# SCH_circuit_board_2023-10-30.net
KiCad netlist of a schematic drawn in EasyEDA
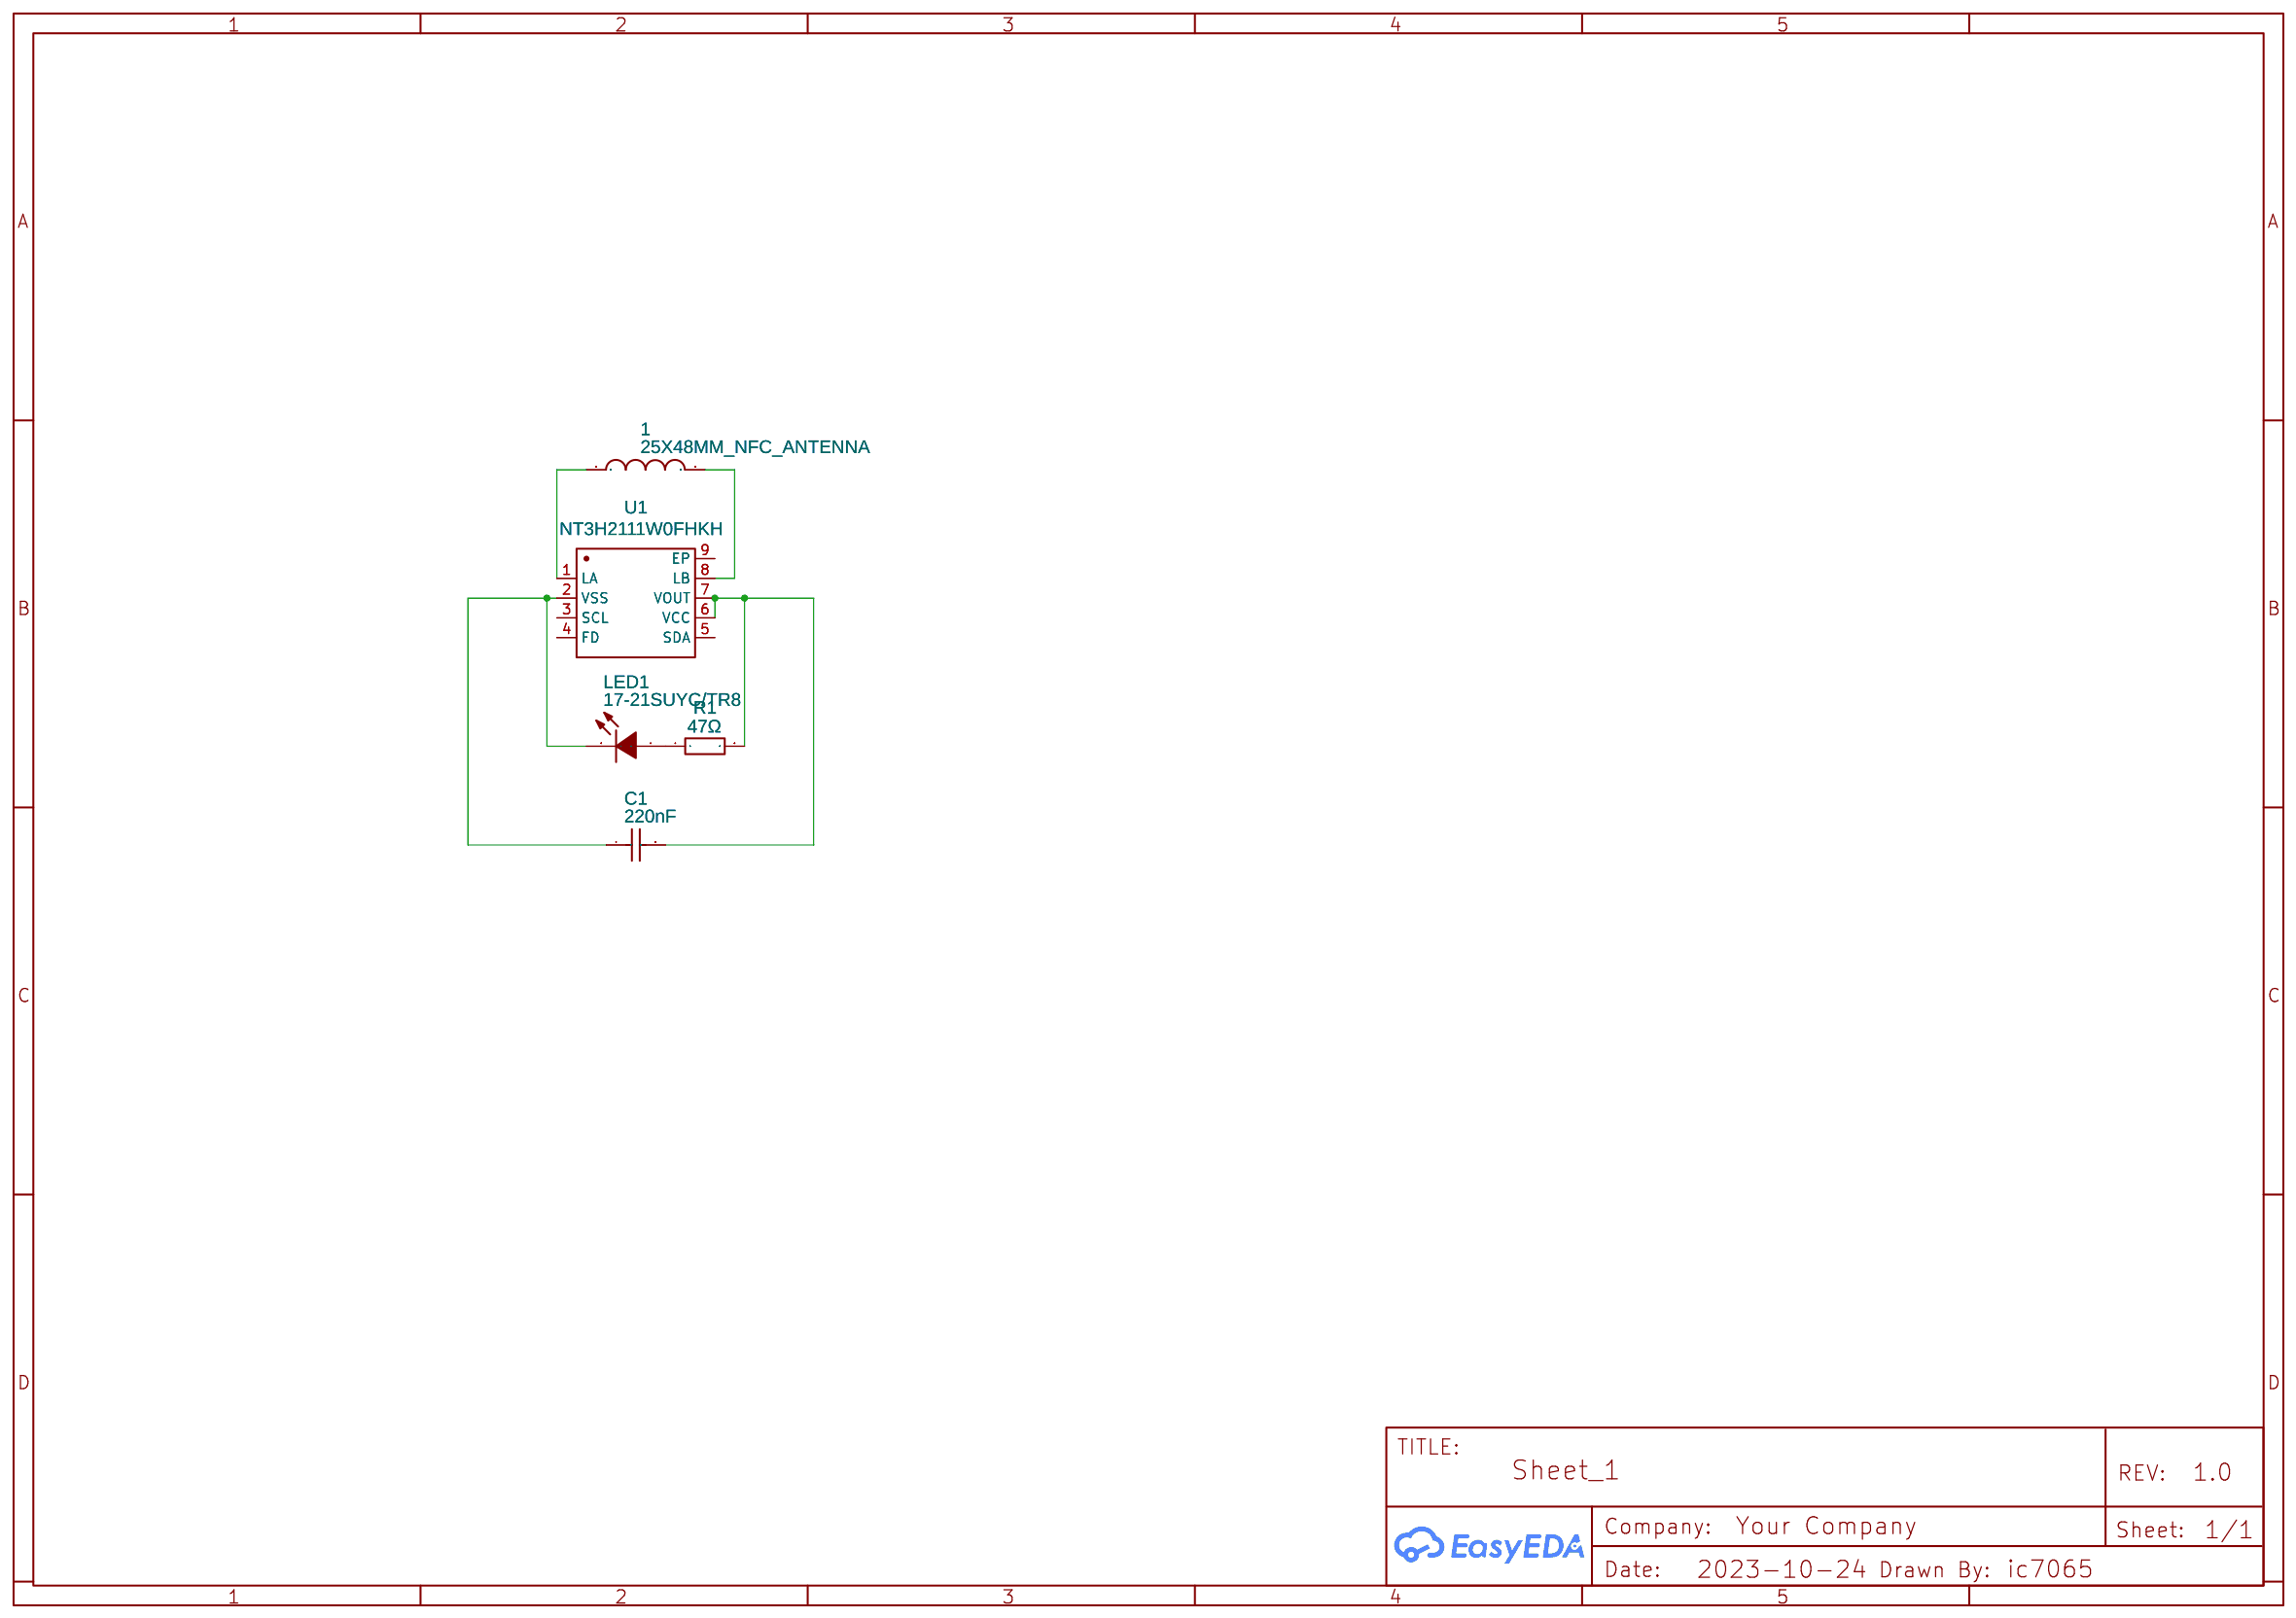
[diagram p0: schematic sheet]

(export (version "E")
  (design (tool "Eeschema 10.0.6"))
  (components
    (comp (ref "1") (value "25X48MM_NFC_ANTENNA") (libsource (lib "") (part "25X48MM_NFC_ANTENNA")))
    (comp (ref "C1")
      (value "220nF")
      (fields
        (field (name "Manufacturer Part") "CL10B224KA8NNNC")
        (field (name "Manufacturer") "SAMSUNG(三星)")
      )
      (libsource (lib "") (part "CL10B224KA8NNNC"))
    )
    (comp (ref "LED1")
      (value "17-21SUYC/TR8")
      (fields (field (name "Manufacturer Part") "KT-0805黄灯") (field (name "Manufacturer") "KENTO"))
      (libsource (lib "") (part "17-21SUYC/TR8"))
    )
    (comp (ref "R1")
      (value "47Ω")
      (fields
        (field (name "Manufacturer Part") "0603WAF470JT5E")
        (field (name "Manufacturer") "UNI-ROYAL(厚声)")
      )
      (libsource (lib "") (part "0603WAF470JT5E"))
    )
    (comp (ref "U1")
      (value "NT3H2111W0FHKH")
      (fields (field (name "Manufacturer") "NXP(恩智浦)"))
      (libsource (lib "") (part "NT3H2111W0FHKH"))
    )
  )
  (nets
    (net (code "1") (name "Net-(LED1-+)") (class "Default")
      (node (ref "LED1") (pin "1") (pinfunction "+_1") (pintype "unspecified"))
      (node (ref "R1") (pin "1") (pinfunction "1_1") (pintype "input"))
    )
    (net (code "2") (name "Net-(LED1--)") (class "Default")
      (node (ref "C1") (pin "1") (pinfunction "1_1") (pintype "input"))
      (node (ref "LED1") (pin "2") (pinfunction "-_2") (pintype "unspecified"))
      (node (ref "U1") (pin "2") (pinfunction "VSS_2") (pintype "unspecified"))
    )
    (net (code "3") (name "Net-(U1-LA)") (class "Default")
      (node (ref "1") (pin "P$1") (pinfunction "P$1_P$1") (pintype "bidirectional"))
      (node (ref "U1") (pin "1") (pinfunction "LA_1") (pintype "unspecified"))
    )
    (net (code "4") (name "Net-(U1-LB)") (class "Default")
      (node (ref "1") (pin "P$2") (pinfunction "P$2_P$2") (pintype "bidirectional"))
      (node (ref "U1") (pin "8") (pinfunction "LB_8") (pintype "unspecified"))
    )
    (net (code "5") (name "Net-(U1-VCC)") (class "Default")
      (node (ref "C1") (pin "2") (pinfunction "2_2") (pintype "input"))
      (node (ref "R1") (pin "2") (pinfunction "2_2") (pintype "input"))
      (node (ref "U1") (pin "6") (pinfunction "VCC_6") (pintype "unspecified"))
      (node (ref "U1") (pin "7") (pinfunction "VOUT_7") (pintype "unspecified"))
    )
    (net (code "6") (name "unconnected-(U1-EP-Pad9)") (class "Default")
      (node (ref "U1") (pin "9") (pinfunction "EP_9") (pintype "unspecified"))
    )
    (net (code "7") (name "unconnected-(U1-FD-Pad4)") (class "Default")
      (node (ref "U1") (pin "4") (pinfunction "FD_4") (pintype "unspecified"))
    )
    (net (code "8") (name "unconnected-(U1-SCL-Pad3)") (class "Default")
      (node (ref "U1") (pin "3") (pinfunction "SCL_3") (pintype "unspecified"))
    )
    (net (code "9") (name "unconnected-(U1-SDA-Pad5)") (class "Default")
      (node (ref "U1") (pin "5") (pinfunction "SDA_5") (pintype "unspecified"))
    )
  )
)
